# Minisumo_2018_Educatiu.net
KiCad netlist of a schematic drawn in EAGLE
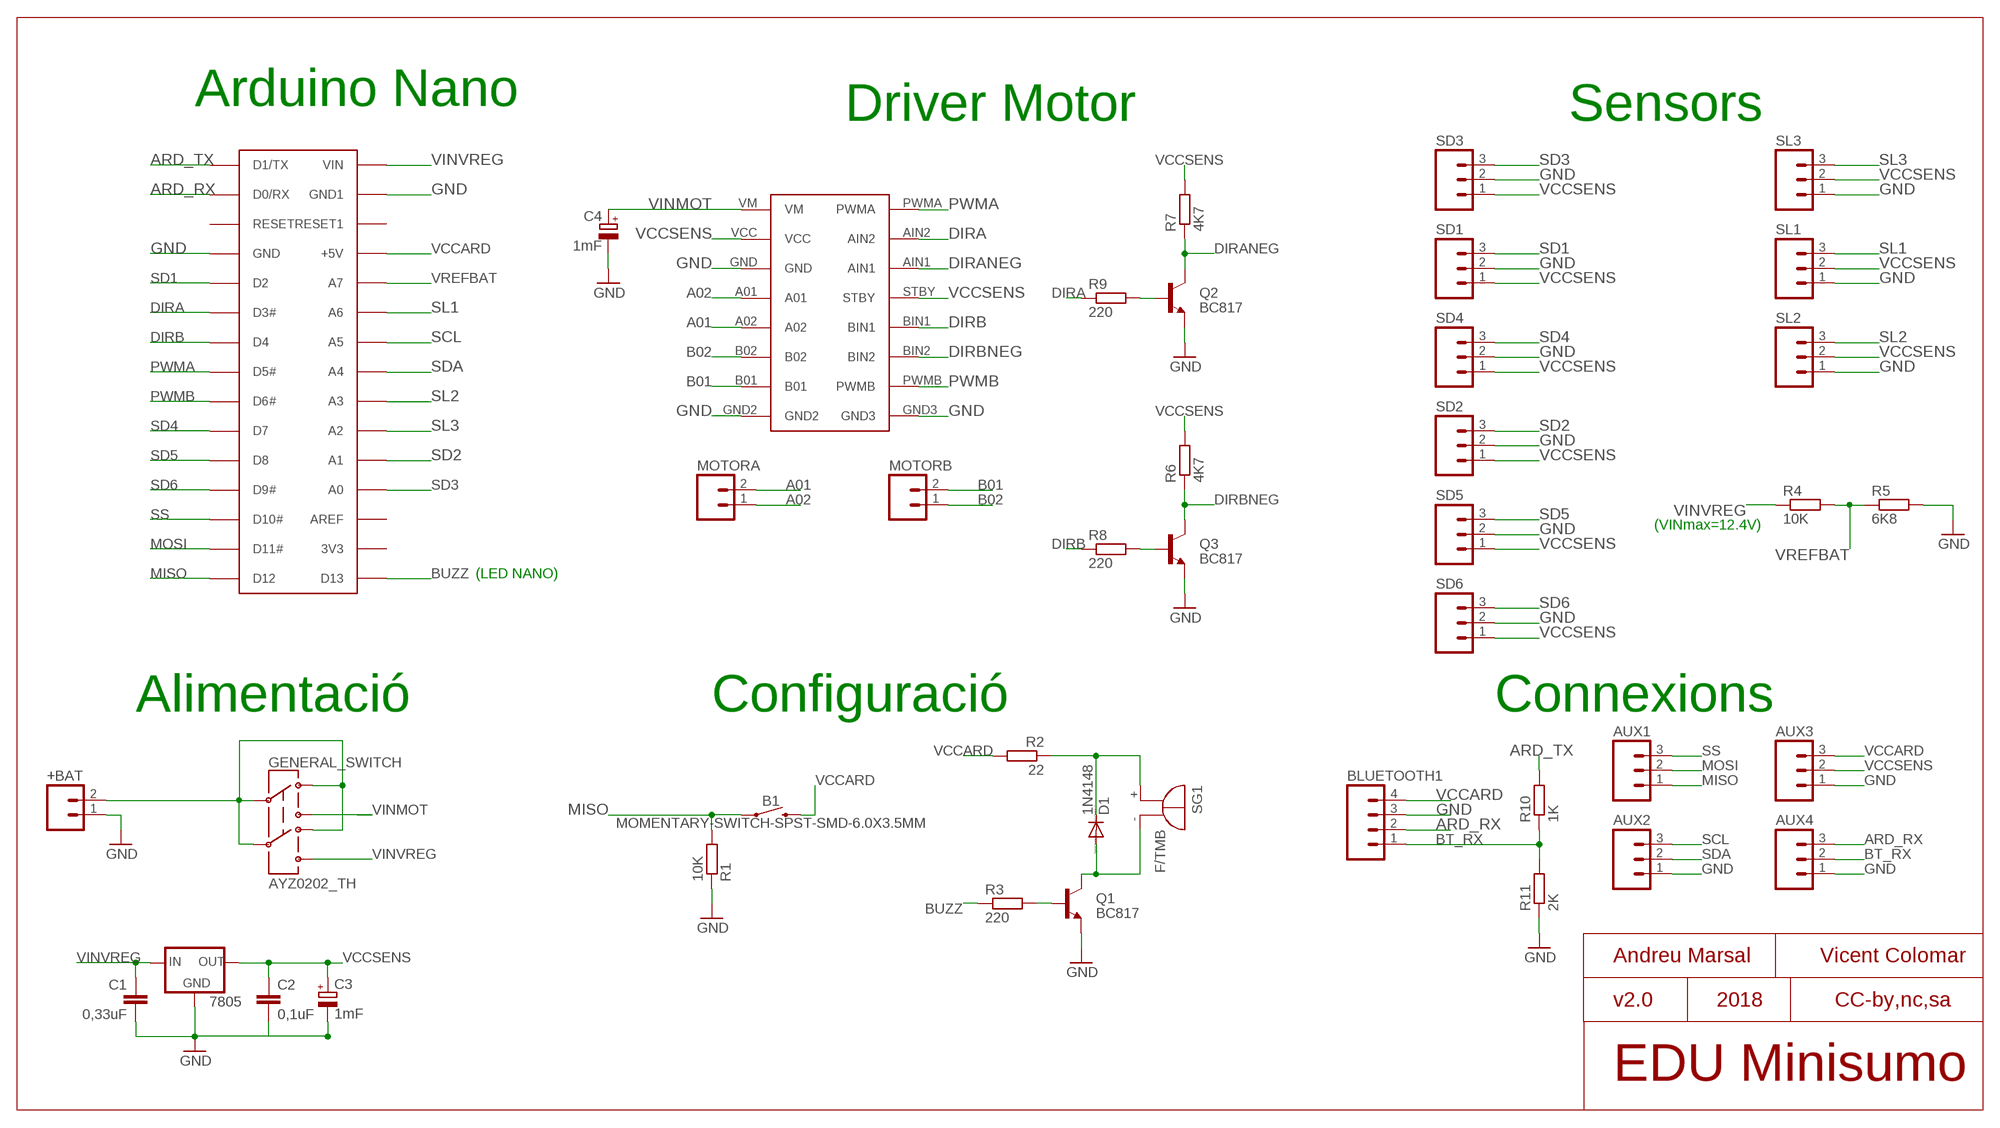
[diagram p0: schematic, sheet 1]
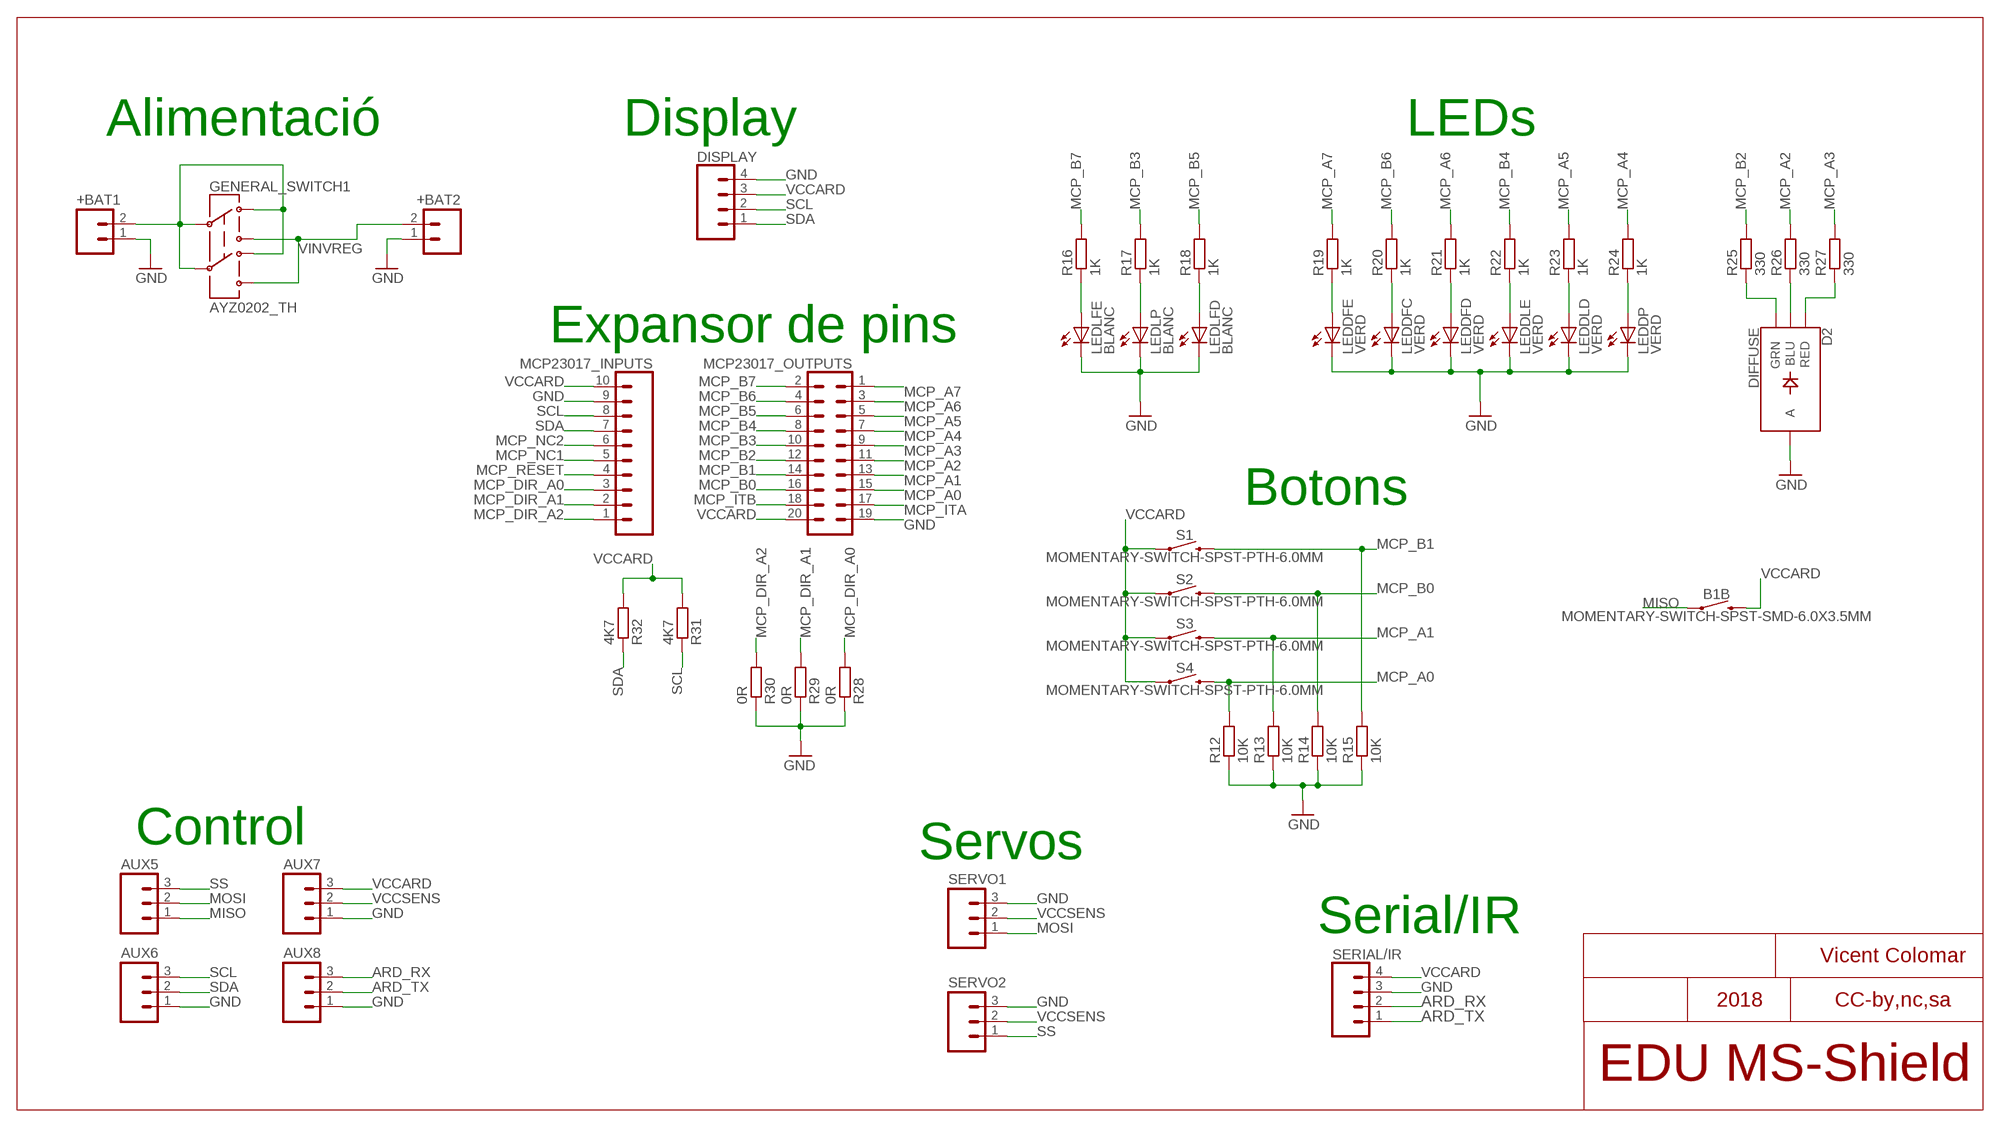
[diagram p1: schematic, sheet 2]

(export (version "E")
  (design (tool "Eeschema 10.0.6"))
  (components
    (comp (ref "+BAT")
      (value "M02LOCK_LONGPADS")
      (footprint "eagle-import:1X02_LOCK_LONGPADS")
      (libsource (lib "eagle-import") (part "M02LOCK_LONGPADS"))
    )
    (comp (ref "7805")
      (value "V_REG_78XXSINK")
      (footprint "eagle-import:TO220-IGO")
      (libsource (lib "eagle-import") (part "V_REG_78XXSINK"))
    )
    (comp (ref "AUX1")
      (value "M03PTH")
      (footprint "eagle-import:1X03")
      (libsource (lib "eagle-import") (part "M03PTH"))
    )
    (comp (ref "AUX2")
      (value "M03PTH")
      (footprint "eagle-import:1X03")
      (libsource (lib "eagle-import") (part "M03PTH"))
    )
    (comp (ref "AUX3")
      (value "M03PTH")
      (footprint "eagle-import:1X03")
      (libsource (lib "eagle-import") (part "M03PTH"))
    )
    (comp (ref "AUX4")
      (value "M03PTH")
      (footprint "eagle-import:1X03")
      (libsource (lib "eagle-import") (part "M03PTH"))
    )
    (comp (ref "B1")
      (value "MOMENTARY-SWITCH-SPST-SMD-6.0X3.5MM")
      (footprint "eagle-import:TACTILE_SWITCH_SMD_6.0X3.5MM")
      (libsource (lib "eagle-import") (part "MOMENTARY-SWITCH-SPST-SMD-6.0X3.5MM"))
    )
    (comp (ref "BLUETOOTH1")
      (value "M04PTH")
      (footprint "eagle-import:1X04")
      (libsource (lib "eagle-import") (part "M04PTH"))
    )
    (comp (ref "C1")
      (value "0,33uF")
      (footprint "eagle-import:C1206K")
      (libsource (lib "eagle-import") (part "C-EUC1206K"))
    )
    (comp (ref "C2")
      (value "0,1uF")
      (footprint "eagle-import:C1206K")
      (libsource (lib "eagle-import") (part "C-EUC1206K"))
    )
    (comp (ref "C3")
      (value "1mF")
      (footprint "eagle-import:E2,5-6")
      (libsource (lib "eagle-import") (part "CPOL-EUE2.5-6"))
    )
    (comp (ref "C4")
      (value "1mF")
      (footprint "eagle-import:E2,5-6")
      (libsource (lib "eagle-import") (part "CPOL-EUE2.5-6"))
    )
    (comp (ref "D1")
      (value "1N4148")
      (footprint "eagle-import:SOD106-R")
      (libsource (lib "eagle-import") (part "DIODE-SOD106-R"))
    )
    (comp (ref "GENERAL_SWITCH")
      (value "AYZ0202_TH")
      (footprint "eagle-import:AYZ0202_TH")
      (libsource (lib "eagle-import") (part "AYZ0202_TH"))
    )
    (comp (ref "MOTORA")
      (value "M023.5MM")
      (footprint "eagle-import:SCREWTERMINAL-3.5MM-2")
      (libsource (lib "eagle-import") (part "M023.5MM"))
    )
    (comp (ref "MOTORB")
      (value "M023.5MM")
      (footprint "eagle-import:SCREWTERMINAL-3.5MM-2")
      (libsource (lib "eagle-import") (part "M023.5MM"))
    )
    (comp (ref "Q1")
      (value "BC817")
      (footprint "eagle-import:TO-92")
      (libsource (lib "eagle-import") (part "TRANSISTOR_NPNTO92"))
    )
    (comp (ref "Q2")
      (value "BC817")
      (footprint "eagle-import:TO-92")
      (libsource (lib "eagle-import") (part "TRANSISTOR_NPNTO92"))
    )
    (comp (ref "Q3")
      (value "BC817")
      (footprint "eagle-import:TO-92")
      (libsource (lib "eagle-import") (part "TRANSISTOR_NPNTO92"))
    )
    (comp (ref "R1")
      (value "10K")
      (footprint "eagle-import:R1206")
      (libsource (lib "eagle-import") (part "resistor_348_R-EU_R1206"))
    )
    (comp (ref "R2")
      (value "22")
      (footprint "eagle-import:R1206")
      (libsource (lib "eagle-import") (part "resistor_348_R-EU_R1206"))
    )
    (comp (ref "R3")
      (value "220")
      (footprint "eagle-import:M1206")
      (libsource (lib "eagle-import") (part "R-EU_M1206"))
    )
    (comp (ref "R4")
      (value "10K")
      (footprint "eagle-import:R1206")
      (libsource (lib "eagle-import") (part "resistor_348_R-EU_R1206"))
    )
    (comp (ref "R5")
      (value "6K8")
      (footprint "eagle-import:R1206")
      (libsource (lib "eagle-import") (part "resistor_348_R-EU_R1206"))
    )
    (comp (ref "R6")
      (value "4K7")
      (footprint "eagle-import:M1206")
      (libsource (lib "eagle-import") (part "R-EU_M1206"))
    )
    (comp (ref "R7")
      (value "4K7")
      (footprint "eagle-import:M1206")
      (libsource (lib "eagle-import") (part "R-EU_M1206"))
    )
    (comp (ref "R8")
      (value "220")
      (footprint "eagle-import:M1206")
      (libsource (lib "eagle-import") (part "R-EU_M1206"))
    )
    (comp (ref "R9")
      (value "220")
      (footprint "eagle-import:M1206")
      (libsource (lib "eagle-import") (part "R-EU_M1206"))
    )
    (comp (ref "R10")
      (value "1K")
      (footprint "eagle-import:R1206")
      (libsource (lib "eagle-import") (part "resistor_348_R-EU_R1206"))
    )
    (comp (ref "R11")
      (value "2K")
      (footprint "eagle-import:R1206")
      (libsource (lib "eagle-import") (part "resistor_348_R-EU_R1206"))
    )
    (comp (ref "SD1")
      (value "M03PTH")
      (footprint "eagle-import:1X03")
      (libsource (lib "eagle-import") (part "M03PTH"))
    )
    (comp (ref "SD2")
      (value "M03PTH")
      (footprint "eagle-import:1X03")
      (libsource (lib "eagle-import") (part "M03PTH"))
    )
    (comp (ref "SD3")
      (value "M03PTH")
      (footprint "eagle-import:1X03")
      (libsource (lib "eagle-import") (part "M03PTH"))
    )
    (comp (ref "SD4")
      (value "M03PTH")
      (footprint "eagle-import:1X03")
      (libsource (lib "eagle-import") (part "M03PTH"))
    )
    (comp (ref "SD5")
      (value "M03PTH")
      (footprint "eagle-import:1X03")
      (libsource (lib "eagle-import") (part "M03PTH"))
    )
    (comp (ref "SD6")
      (value "M03PTH")
      (footprint "eagle-import:1X03")
      (libsource (lib "eagle-import") (part "M03PTH"))
    )
    (comp (ref "SG1")
      (value "F/TMB")
      (footprint "eagle-import:F_TMB")
      (libsource (lib "eagle-import") (part "F/TMB"))
    )
    (comp (ref "SL1")
      (value "M03PTH")
      (footprint "eagle-import:1X03")
      (libsource (lib "eagle-import") (part "M03PTH"))
    )
    (comp (ref "SL2")
      (value "M03PTH")
      (footprint "eagle-import:1X03")
      (libsource (lib "eagle-import") (part "M03PTH"))
    )
    (comp (ref "SL3")
      (value "M03PTH")
      (footprint "eagle-import:1X03")
      (libsource (lib "eagle-import") (part "M03PTH"))
    )
    (comp (ref "U$1")
      (value "ARDUINONANONOHOLES")
      (footprint "eagle-import:PDIP-32NOHOLES")
      (libsource (lib "eagle-import") (part "ARDUINONANONOHOLES"))
    )
    (comp (ref "U$2")
      (value "TB6612FNG_SPARKFUN")
      (footprint "eagle-import:TB6612FNG_SPARKFUN")
      (libsource (lib "eagle-import") (part "TB6612FNG_SPARKFUN"))
    )
    (comp (ref "+BAT1")
      (value "M02LOCK_LONGPADS")
      (footprint "eagle-import:1X02_LOCK_LONGPADS")
      (libsource (lib "eagle-import") (part "M02LOCK_LONGPADS"))
    )
    (comp (ref "+BAT2")
      (value "M02LOCK_LONGPADS")
      (footprint "eagle-import:1X02_LOCK_LONGPADS")
      (libsource (lib "eagle-import") (part "M02LOCK_LONGPADS"))
    )
    (comp (ref "AUX5")
      (value "M03PTH")
      (footprint "eagle-import:1X03")
      (libsource (lib "eagle-import") (part "M03PTH"))
    )
    (comp (ref "AUX6")
      (value "M03PTH")
      (footprint "eagle-import:1X03")
      (libsource (lib "eagle-import") (part "M03PTH"))
    )
    (comp (ref "AUX7")
      (value "M03PTH")
      (footprint "eagle-import:1X03")
      (libsource (lib "eagle-import") (part "M03PTH"))
    )
    (comp (ref "AUX8")
      (value "M03PTH")
      (footprint "eagle-import:1X03")
      (libsource (lib "eagle-import") (part "M03PTH"))
    )
    (comp (ref "B1B")
      (value "MOMENTARY-SWITCH-SPST-SMD-6.0X3.5MM")
      (footprint "eagle-import:TACTILE_SWITCH_SMD_6.0X3.5MM")
      (libsource (lib "eagle-import") (part "MOMENTARY-SWITCH-SPST-SMD-6.0X3.5MM"))
    )
    (comp (ref "D2")
      (value "DIFFUSE")
      (footprint "eagle-import:LED-RGB-THRU")
      (libsource (lib "eagle-import") (part "LED-RGB-CADIFFUSE"))
    )
    (comp (ref "DISPLAY")
      (value "CONN_04")
      (footprint "eagle-import:1X04")
      (libsource (lib "eagle-import") (part "CONN_04"))
    )
    (comp (ref "GENERAL_SWITCH1")
      (value "AYZ0202_TH")
      (footprint "eagle-import:AYZ0202_TH")
      (libsource (lib "eagle-import") (part "AYZ0202_TH"))
    )
    (comp (ref "LEDDFC")
      (value "VERD")
      (footprint "eagle-import:1206")
      (libsource (lib "eagle-import") (part "LEDSMT1206"))
    )
    (comp (ref "LEDDFD")
      (value "VERD")
      (footprint "eagle-import:1206")
      (libsource (lib "eagle-import") (part "LEDSMT1206"))
    )
    (comp (ref "LEDDFE")
      (value "VERD")
      (footprint "eagle-import:1206")
      (libsource (lib "eagle-import") (part "LEDSMT1206"))
    )
    (comp (ref "LEDDLD")
      (value "VERD")
      (footprint "eagle-import:1206")
      (libsource (lib "eagle-import") (part "LEDSMT1206"))
    )
    (comp (ref "LEDDLE")
      (value "VERD")
      (footprint "eagle-import:1206")
      (libsource (lib "eagle-import") (part "LEDSMT1206"))
    )
    (comp (ref "LEDDP")
      (value "VERD")
      (footprint "eagle-import:1206")
      (libsource (lib "eagle-import") (part "LEDSMT1206"))
    )
    (comp (ref "LEDLFD")
      (value "BLANC")
      (footprint "eagle-import:1206")
      (libsource (lib "eagle-import") (part "LEDSMT1206"))
    )
    (comp (ref "LEDLFE")
      (value "BLANC")
      (footprint "eagle-import:1206")
      (libsource (lib "eagle-import") (part "LEDSMT1206"))
    )
    (comp (ref "LEDLP")
      (value "BLANC")
      (footprint "eagle-import:1206")
      (libsource (lib "eagle-import") (part "LEDSMT1206"))
    )
    (comp (ref "MCP23017_INPUTS")
      (value "CONN_10\"")
      (footprint "eagle-import:1X10")
      (libsource (lib "eagle-import") (part "CONN_10{dblquote}"))
    )
    (comp (ref "MCP23017_OUTPUTS")
      (value "CONN_10X2")
      (footprint "eagle-import:2X10")
      (libsource (lib "eagle-import") (part "CONN_10X2"))
    )
    (comp (ref "R12")
      (value "10K")
      (footprint "eagle-import:M1206")
      (libsource (lib "eagle-import") (part "R-EU_M1206"))
    )
    (comp (ref "R13")
      (value "10K")
      (footprint "eagle-import:M1206")
      (libsource (lib "eagle-import") (part "R-EU_M1206"))
    )
    (comp (ref "R14")
      (value "10K")
      (footprint "eagle-import:M1206")
      (libsource (lib "eagle-import") (part "R-EU_M1206"))
    )
    (comp (ref "R15")
      (value "10K")
      (footprint "eagle-import:M1206")
      (libsource (lib "eagle-import") (part "R-EU_M1206"))
    )
    (comp (ref "R16")
      (value "1K")
      (footprint "eagle-import:M1206")
      (libsource (lib "eagle-import") (part "R-EU_M1206"))
    )
    (comp (ref "R17")
      (value "1K")
      (footprint "eagle-import:M1206")
      (libsource (lib "eagle-import") (part "R-EU_M1206"))
    )
    (comp (ref "R18")
      (value "1K")
      (footprint "eagle-import:M1206")
      (libsource (lib "eagle-import") (part "R-EU_M1206"))
    )
    (comp (ref "R19")
      (value "1K")
      (footprint "eagle-import:M1206")
      (libsource (lib "eagle-import") (part "R-EU_M1206"))
    )
    (comp (ref "R20")
      (value "1K")
      (footprint "eagle-import:M1206")
      (libsource (lib "eagle-import") (part "R-EU_M1206"))
    )
    (comp (ref "R21")
      (value "1K")
      (footprint "eagle-import:M1206")
      (libsource (lib "eagle-import") (part "R-EU_M1206"))
    )
    (comp (ref "R22")
      (value "1K")
      (footprint "eagle-import:M1206")
      (libsource (lib "eagle-import") (part "R-EU_M1206"))
    )
    (comp (ref "R23")
      (value "1K")
      (footprint "eagle-import:M1206")
      (libsource (lib "eagle-import") (part "R-EU_M1206"))
    )
    (comp (ref "R24")
      (value "1K")
      (footprint "eagle-import:M1206")
      (libsource (lib "eagle-import") (part "R-EU_M1206"))
    )
    (comp (ref "R25")
      (value "330")
      (footprint "eagle-import:M1206")
      (libsource (lib "eagle-import") (part "R-EU_M1206"))
    )
    (comp (ref "R26")
      (value "330")
      (footprint "eagle-import:M1206")
      (libsource (lib "eagle-import") (part "R-EU_M1206"))
    )
    (comp (ref "R27")
      (value "330")
      (footprint "eagle-import:M1206")
      (libsource (lib "eagle-import") (part "R-EU_M1206"))
    )
    (comp (ref "R28")
      (value "0R")
      (footprint "eagle-import:M1206")
      (libsource (lib "eagle-import") (part "R-EU_M1206"))
    )
    (comp (ref "R29")
      (value "0R")
      (footprint "eagle-import:M1206")
      (libsource (lib "eagle-import") (part "R-EU_M1206"))
    )
    (comp (ref "R30")
      (value "0R")
      (footprint "eagle-import:M1206")
      (libsource (lib "eagle-import") (part "R-EU_M1206"))
    )
    (comp (ref "R31")
      (value "4K7")
      (footprint "eagle-import:M1206")
      (libsource (lib "eagle-import") (part "R-EU_M1206"))
    )
    (comp (ref "R32")
      (value "4K7")
      (footprint "eagle-import:M1206")
      (libsource (lib "eagle-import") (part "R-EU_M1206"))
    )
    (comp (ref "S1")
      (value "MOMENTARY-SWITCH-SPST-PTH-6.0MM")
      (footprint "eagle-import:TACTILE_SWITCH_PTH_6.0MM")
      (libsource (lib "eagle-import") (part "MOMENTARY-SWITCH-SPST-PTH-6.0MM"))
    )
    (comp (ref "S2")
      (value "MOMENTARY-SWITCH-SPST-PTH-6.0MM")
      (footprint "eagle-import:TACTILE_SWITCH_PTH_6.0MM")
      (libsource (lib "eagle-import") (part "MOMENTARY-SWITCH-SPST-PTH-6.0MM"))
    )
    (comp (ref "S3")
      (value "MOMENTARY-SWITCH-SPST-PTH-6.0MM")
      (footprint "eagle-import:TACTILE_SWITCH_PTH_6.0MM")
      (libsource (lib "eagle-import") (part "MOMENTARY-SWITCH-SPST-PTH-6.0MM"))
    )
    (comp (ref "S4")
      (value "MOMENTARY-SWITCH-SPST-PTH-6.0MM")
      (footprint "eagle-import:TACTILE_SWITCH_PTH_6.0MM")
      (libsource (lib "eagle-import") (part "MOMENTARY-SWITCH-SPST-PTH-6.0MM"))
    )
    (comp (ref "SERIAL/IR")
      (value "CONN_04")
      (footprint "eagle-import:1X04")
      (libsource (lib "eagle-import") (part "CONN_04"))
    )
    (comp (ref "SERVO1")
      (value "M03PTH")
      (footprint "eagle-import:1X03")
      (libsource (lib "eagle-import") (part "M03PTH"))
    )
    (comp (ref "SERVO2")
      (value "M03PTH")
      (footprint "eagle-import:1X03")
      (libsource (lib "eagle-import") (part "M03PTH"))
    )
  )
  (nets
    (net (code "1") (name "A01") (class "Default")
      (node (ref "MOTORA") (pin "2") (pinfunction "2_2") (pintype "passive"))
      (node (ref "U$2") (pin "A02") (pinfunction "A02_A02") (pintype "bidirectional"))
    )
    (net (code "2") (name "A02") (class "Default")
      (node (ref "MOTORA") (pin "1") (pinfunction "1_1") (pintype "passive"))
      (node (ref "U$2") (pin "A01") (pinfunction "A01_A01") (pintype "bidirectional"))
    )
    (net (code "3") (name "ARD_RX") (class "Default")
      (node (ref "AUX4") (pin "3") (pinfunction "3_3") (pintype "passive"))
      (node (ref "AUX8") (pin "3") (pinfunction "3_3") (pintype "passive"))
      (node (ref "BLUETOOTH1") (pin "2") (pinfunction "2_2") (pintype "passive"))
      (node (ref "SERIAL/IR") (pin "2") (pinfunction "2_2") (pintype "passive"))
      (node (ref "U$1") (pin "D0/RX") (pinfunction "D0/RX_D0/RX") (pintype "bidirectional"))
    )
    (net (code "4") (name "ARD_TX") (class "Default")
      (node (ref "AUX8") (pin "2") (pinfunction "2_2") (pintype "passive"))
      (node (ref "R10") (pin "2") (pinfunction "2_2") (pintype "passive"))
      (node (ref "SERIAL/IR") (pin "1") (pinfunction "1_1") (pintype "passive"))
      (node (ref "U$1") (pin "D1/TX") (pinfunction "D1/TX_D1/TX") (pintype "bidirectional"))
    )
    (net (code "5") (name "B01") (class "Default")
      (node (ref "MOTORB") (pin "2") (pinfunction "2_2") (pintype "passive"))
      (node (ref "U$2") (pin "B01") (pinfunction "B01_B01") (pintype "bidirectional"))
    )
    (net (code "6") (name "B02") (class "Default")
      (node (ref "MOTORB") (pin "1") (pinfunction "1_1") (pintype "passive"))
      (node (ref "U$2") (pin "B02") (pinfunction "B02_B02") (pintype "bidirectional"))
    )
    (net (code "7") (name "BT_RX") (class "Default")
      (node (ref "AUX4") (pin "2") (pinfunction "2_2") (pintype "passive"))
      (node (ref "BLUETOOTH1") (pin "1") (pinfunction "1_1") (pintype "passive"))
      (node (ref "R10") (pin "1") (pinfunction "1_1") (pintype "passive"))
      (node (ref "R11") (pin "2") (pinfunction "2_2") (pintype "passive"))
    )
    (net (code "8") (name "BUZZ") (class "Default")
      (node (ref "R3") (pin "1") (pinfunction "1_1") (pintype "passive"))
      (node (ref "U$1") (pin "D13") (pinfunction "D13_D13") (pintype "bidirectional"))
    )
    (net (code "9") (name "DIRA") (class "Default")
      (node (ref "R9") (pin "1") (pinfunction "1_1") (pintype "passive"))
      (node (ref "U$1") (pin "D3") (pinfunction "D3#_D3") (pintype "bidirectional"))
      (node (ref "U$2") (pin "AIN2") (pinfunction "AIN2_AIN2") (pintype "bidirectional"))
    )
    (net (code "10") (name "DIRANEG") (class "Default")
      (node (ref "Q2") (pin "3") (pinfunction "C_3") (pintype "passive"))
      (node (ref "R7") (pin "1") (pinfunction "1_1") (pintype "passive"))
      (node (ref "U$2") (pin "AIN1") (pinfunction "AIN1_AIN1") (pintype "bidirectional"))
    )
    (net (code "11") (name "DIRB") (class "Default")
      (node (ref "R8") (pin "1") (pinfunction "1_1") (pintype "passive"))
      (node (ref "U$1") (pin "D4") (pinfunction "D4_D4") (pintype "bidirectional"))
      (node (ref "U$2") (pin "BIN1") (pinfunction "BIN1_BIN1") (pintype "bidirectional"))
    )
    (net (code "12") (name "DIRBNEG") (class "Default")
      (node (ref "Q3") (pin "3") (pinfunction "C_3") (pintype "passive"))
      (node (ref "R6") (pin "1") (pinfunction "1_1") (pintype "passive"))
      (node (ref "U$2") (pin "BIN2") (pinfunction "BIN2_BIN2") (pintype "bidirectional"))
    )
    (net (code "13") (name "GND") (class "Default")
      (node (ref "+BAT") (pin "1") (pinfunction "1_1") (pintype "passive"))
      (node (ref "+BAT1") (pin "1") (pinfunction "1_1") (pintype "passive"))
      (node (ref "+BAT2") (pin "1") (pinfunction "1_1") (pintype "passive"))
      (node (ref "7805") (pin "GND") (pinfunction "GND_GND") (pintype "input"))
      (node (ref "AUX2") (pin "1") (pinfunction "1_1") (pintype "passive"))
      (node (ref "AUX3") (pin "1") (pinfunction "1_1") (pintype "passive"))
      (node (ref "AUX4") (pin "1") (pinfunction "1_1") (pintype "passive"))
      (node (ref "AUX6") (pin "1") (pinfunction "1_1") (pintype "passive"))
      (node (ref "AUX7") (pin "1") (pinfunction "1_1") (pintype "passive"))
      (node (ref "AUX8") (pin "1") (pinfunction "1_1") (pintype "passive"))
      (node (ref "BLUETOOTH1") (pin "3") (pinfunction "3_3") (pintype "passive"))
      (node (ref "C1") (pin "2") (pinfunction "2_2") (pintype "passive"))
      (node (ref "C2") (pin "2") (pinfunction "2_2") (pintype "passive"))
      (node (ref "C3") (pin "-") (pinfunction "-_-") (pintype "passive"))
      (node (ref "C4") (pin "-") (pinfunction "-_-") (pintype "passive"))
      (node (ref "D2") (pin "2") (pinfunction "A_2") (pintype "bidirectional"))
      (node (ref "DISPLAY") (pin "4") (pinfunction "4_4") (pintype "passive"))
      (node (ref "LEDDFC") (pin "C") (pinfunction "C_C") (pintype "passive"))
      (node (ref "LEDDFD") (pin "C") (pinfunction "C_C") (pintype "passive"))
      (node (ref "LEDDFE") (pin "C") (pinfunction "C_C") (pintype "passive"))
      (node (ref "LEDDLD") (pin "C") (pinfunction "C_C") (pintype "passive"))
      (node (ref "LEDDLE") (pin "C") (pinfunction "C_C") (pintype "passive"))
      (node (ref "LEDDP") (pin "C") (pinfunction "C_C") (pintype "passive"))
      (node (ref "LEDLFD") (pin "C") (pinfunction "C_C") (pintype "passive"))
      (node (ref "LEDLFE") (pin "C") (pinfunction "C_C") (pintype "passive"))
      (node (ref "LEDLP") (pin "C") (pinfunction "C_C") (pintype "passive"))
      (node (ref "MCP23017_INPUTS") (pin "9") (pinfunction "9_9") (pintype "passive"))
      (node (ref "MCP23017_OUTPUTS") (pin "19") (pinfunction "19_19") (pintype "passive"))
      (node (ref "Q1") (pin "1") (pinfunction "E_1") (pintype "passive"))
      (node (ref "Q2") (pin "1") (pinfunction "E_1") (pintype "passive"))
      (node (ref "Q3") (pin "1") (pinfunction "E_1") (pintype "passive"))
      (node (ref "R1") (pin "1") (pinfunction "1_1") (pintype "passive"))
      (node (ref "R11") (pin "1") (pinfunction "1_1") (pintype "passive"))
      (node (ref "R12") (pin "1") (pinfunction "1_1") (pintype "passive"))
      (node (ref "R13") (pin "1") (pinfunction "1_1") (pintype "passive"))
      (node (ref "R14") (pin "1") (pinfunction "1_1") (pintype "passive"))
      (node (ref "R15") (pin "1") (pinfunction "1_1") (pintype "passive"))
      (node (ref "R28") (pin "1") (pinfunction "1_1") (pintype "passive"))
      (node (ref "R29") (pin "1") (pinfunction "1_1") (pintype "passive"))
      (node (ref "R30") (pin "1") (pinfunction "1_1") (pintype "passive"))
      (node (ref "R5") (pin "2") (pinfunction "2_2") (pintype "passive"))
      (node (ref "SD1") (pin "2") (pinfunction "2_2") (pintype "passive"))
      (node (ref "SD2") (pin "2") (pinfunction "2_2") (pintype "passive"))
      (node (ref "SD3") (pin "2") (pinfunction "2_2") (pintype "passive"))
      (node (ref "SD4") (pin "2") (pinfunction "2_2") (pintype "passive"))
      (node (ref "SD5") (pin "2") (pinfunction "2_2") (pintype "passive"))
      (node (ref "SD6") (pin "2") (pinfunction "2_2") (pintype "passive"))
      (node (ref "SERIAL/IR") (pin "3") (pinfunction "3_3") (pintype "passive"))
      (node (ref "SERVO1") (pin "3") (pinfunction "3_3") (pintype "passive"))
      (node (ref "SERVO2") (pin "3") (pinfunction "3_3") (pintype "passive"))
      (node (ref "SL1") (pin "1") (pinfunction "1_1") (pintype "passive"))
      (node (ref "SL2") (pin "1") (pinfunction "1_1") (pintype "passive"))
      (node (ref "SL3") (pin "1") (pinfunction "1_1") (pintype "passive"))
      (node (ref "U$1") (pin "GND") (pinfunction "GND_GND") (pintype "bidirectional"))
      (node (ref "U$1") (pin "GND1") (pinfunction "GND1_GND1") (pintype "bidirectional"))
      (node (ref "U$2") (pin "GND") (pinfunction "GND_GND") (pintype "bidirectional"))
      (node (ref "U$2") (pin "GND2") (pinfunction "GND2_GND2") (pintype "bidirectional"))
      (node (ref "U$2") (pin "GND3") (pinfunction "GND3_GND3") (pintype "bidirectional"))
    )
    (net (code "14") (name "MCP_A0") (class "Default")
      (node (ref "MCP23017_OUTPUTS") (pin "15") (pinfunction "15_15") (pintype "passive"))
      (node (ref "R12") (pin "2") (pinfunction "2_2") (pintype "passive"))
      (node (ref "S4") (pin "3") (pinfunction "2_3") (pintype "passive"))
    )
    (net (code "15") (name "MCP_A1") (class "Default")
      (node (ref "MCP23017_OUTPUTS") (pin "13") (pinfunction "13_13") (pintype "passive"))
      (node (ref "R13") (pin "2") (pinfunction "2_2") (pintype "passive"))
      (node (ref "S3") (pin "3") (pinfunction "2_3") (pintype "passive"))
    )
    (net (code "16") (name "MCP_A2") (class "Default")
      (node (ref "MCP23017_OUTPUTS") (pin "11") (pinfunction "11_11") (pintype "passive"))
      (node (ref "R26") (pin "2") (pinfunction "2_2") (pintype "passive"))
    )
    (net (code "17") (name "MCP_A3") (class "Default")
      (node (ref "MCP23017_OUTPUTS") (pin "9") (pinfunction "9_9") (pintype "passive"))
      (node (ref "R27") (pin "2") (pinfunction "2_2") (pintype "passive"))
    )
    (net (code "18") (name "MCP_A4") (class "Default")
      (node (ref "MCP23017_OUTPUTS") (pin "7") (pinfunction "7_7") (pintype "passive"))
      (node (ref "R24") (pin "2") (pinfunction "2_2") (pintype "passive"))
    )
    (net (code "19") (name "MCP_A5") (class "Default")
      (node (ref "MCP23017_OUTPUTS") (pin "5") (pinfunction "5_5") (pintype "passive"))
      (node (ref "R23") (pin "2") (pinfunction "2_2") (pintype "passive"))
    )
    (net (code "20") (name "MCP_A6") (class "Default")
      (node (ref "MCP23017_OUTPUTS") (pin "3") (pinfunction "3_3") (pintype "passive"))
      (node (ref "R21") (pin "2") (pinfunction "2_2") (pintype "passive"))
    )
    (net (code "21") (name "MCP_A7") (class "Default")
      (node (ref "MCP23017_OUTPUTS") (pin "1") (pinfunction "1_1") (pintype "passive"))
      (node (ref "R19") (pin "2") (pinfunction "2_2") (pintype "passive"))
    )
    (net (code "22") (name "MCP_B0") (class "Default")
      (node (ref "MCP23017_OUTPUTS") (pin "16") (pinfunction "16_16") (pintype "passive"))
      (node (ref "R14") (pin "2") (pinfunction "2_2") (pintype "passive"))
      (node (ref "S2") (pin "3") (pinfunction "2_3") (pintype "passive"))
    )
    (net (code "23") (name "MCP_B1") (class "Default")
      (node (ref "MCP23017_OUTPUTS") (pin "14") (pinfunction "14_14") (pintype "passive"))
      (node (ref "R15") (pin "2") (pinfunction "2_2") (pintype "passive"))
      (node (ref "S1") (pin "3") (pinfunction "2_3") (pintype "passive"))
    )
    (net (code "24") (name "MCP_B2") (class "Default")
      (node (ref "MCP23017_OUTPUTS") (pin "12") (pinfunction "12_12") (pintype "passive"))
      (node (ref "R25") (pin "2") (pinfunction "2_2") (pintype "passive"))
    )
    (net (code "25") (name "MCP_B3") (class "Default")
      (node (ref "MCP23017_OUTPUTS") (pin "10") (pinfunction "10_10") (pintype "passive"))
      (node (ref "R17") (pin "2") (pinfunction "2_2") (pintype "passive"))
    )
    (net (code "26") (name "MCP_B4") (class "Default")
      (node (ref "MCP23017_OUTPUTS") (pin "8") (pinfunction "8_8") (pintype "passive"))
      (node (ref "R22") (pin "2") (pinfunction "2_2") (pintype "passive"))
    )
    (net (code "27") (name "MCP_B5") (class "Default")
      (node (ref "MCP23017_OUTPUTS") (pin "6") (pinfunction "6_6") (pintype "passive"))
      (node (ref "R18") (pin "2") (pinfunction "2_2") (pintype "passive"))
    )
    (net (code "28") (name "MCP_B6") (class "Default")
      (node (ref "MCP23017_OUTPUTS") (pin "4") (pinfunction "4_4") (pintype "passive"))
      (node (ref "R20") (pin "2") (pinfunction "2_2") (pintype "passive"))
    )
    (net (code "29") (name "MCP_B7") (class "Default")
      (node (ref "MCP23017_OUTPUTS") (pin "2") (pinfunction "2_2") (pintype "passive"))
      (node (ref "R16") (pin "2") (pinfunction "2_2") (pintype "passive"))
    )
    (net (code "30") (name "MCP_DIR_A0") (class "Default")
      (node (ref "MCP23017_INPUTS") (pin "3") (pinfunction "3_3") (pintype "passive"))
      (node (ref "R28") (pin "2") (pinfunction "2_2") (pintype "passive"))
    )
    (net (code "31") (name "MCP_DIR_A1") (class "Default")
      (node (ref "MCP23017_INPUTS") (pin "2") (pinfunction "2_2") (pintype "passive"))
      (node (ref "R29") (pin "2") (pinfunction "2_2") (pintype "passive"))
    )
    (net (code "32") (name "MCP_DIR_A2") (class "Default")
      (node (ref "MCP23017_INPUTS") (pin "1") (pinfunction "1_1") (pintype "passive"))
      (node (ref "R30") (pin "2") (pinfunction "2_2") (pintype "passive"))
    )
    (net (code "33") (name "MCP_ITA") (class "Default")
      (node (ref "MCP23017_OUTPUTS") (pin "17") (pinfunction "17_17") (pintype "passive"))
    )
    (net (code "34") (name "MCP_ITB") (class "Default")
      (node (ref "MCP23017_OUTPUTS") (pin "18") (pinfunction "18_18") (pintype "passive"))
    )
    (net (code "35") (name "MCP_NC1") (class "Default")
      (node (ref "MCP23017_INPUTS") (pin "5") (pinfunction "5_5") (pintype "passive"))
    )
    (net (code "36") (name "MCP_NC2") (class "Default")
      (node (ref "MCP23017_INPUTS") (pin "6") (pinfunction "6_6") (pintype "passive"))
    )
    (net (code "37") (name "MCP_RESET") (class "Default")
      (node (ref "MCP23017_INPUTS") (pin "4") (pinfunction "4_4") (pintype "passive"))
    )
    (net (code "38") (name "MISO") (class "Default")
      (node (ref "AUX1") (pin "1") (pinfunction "1_1") (pintype "passive"))
      (node (ref "AUX5") (pin "1") (pinfunction "1_1") (pintype "passive"))
      (node (ref "B1") (pin "1") (pinfunction "1_1") (pintype "passive"))
      (node (ref "B1B") (pin "1") (pinfunction "1_1") (pintype "passive"))
      (node (ref "R1") (pin "2") (pinfunction "2_2") (pintype "passive"))
      (node (ref "U$1") (pin "D12") (pinfunction "D12_D12") (pintype "bidirectional"))
    )
    (net (code "39") (name "MOSI") (class "Default")
      (node (ref "AUX1") (pin "2") (pinfunction "2_2") (pintype "passive"))
      (node (ref "AUX5") (pin "2") (pinfunction "2_2") (pintype "passive"))
      (node (ref "SERVO1") (pin "1") (pinfunction "1_1") (pintype "passive"))
      (node (ref "U$1") (pin "D11") (pinfunction "D11#_D11") (pintype "bidirectional"))
    )
    (net (code "40") (name "Net-(+BAT-Pad2)") (class "Default")
      (node (ref "+BAT") (pin "2") (pinfunction "2_2") (pintype "passive"))
      (node (ref "GENERAL_SWITCH") (pin "C1") (pinfunction "C1_C1") (pintype "bidirectional"))
      (node (ref "GENERAL_SWITCH") (pin "C2") (pinfunction "C2_C2") (pintype "bidirectional"))
      (node (ref "GENERAL_SWITCH") (pin "D1") (pinfunction "D1_D1") (pintype "bidirectional"))
      (node (ref "GENERAL_SWITCH") (pin "D2") (pinfunction "D2_D2") (pintype "bidirectional"))
    )
    (net (code "41") (name "Net-(+BAT1-Pad2)") (class "Default")
      (node (ref "+BAT1") (pin "2") (pinfunction "2_2") (pintype "passive"))
      (node (ref "GENERAL_SWITCH1") (pin "C1") (pinfunction "C1_C1") (pintype "bidirectional"))
      (node (ref "GENERAL_SWITCH1") (pin "C2") (pinfunction "C2_C2") (pintype "bidirectional"))
      (node (ref "GENERAL_SWITCH1") (pin "D1") (pinfunction "D1_D1") (pintype "bidirectional"))
      (node (ref "GENERAL_SWITCH1") (pin "D2") (pinfunction "D2_D2") (pintype "bidirectional"))
    )
    (net (code "42") (name "Net-(D1-PadC)") (class "Default")
      (node (ref "D1") (pin "C") (pinfunction "C_C") (pintype "passive"))
      (node (ref "R2") (pin "1") (pinfunction "1_1") (pintype "passive"))
      (node (ref "SG1") (pin "+") (pinfunction "+_+") (pintype "passive"))
    )
    (net (code "43") (name "Net-(D2-BLU)") (class "Default")
      (node (ref "D2") (pin "4") (pinfunction "BLU_4") (pintype "bidirectional"))
      (node (ref "R26") (pin "1") (pinfunction "1_1") (pintype "passive"))
    )
    (net (code "44") (name "Net-(D2-GRN)") (class "Default")
      (node (ref "D2") (pin "3") (pinfunction "GRN_3") (pintype "bidirectional"))
      (node (ref "R25") (pin "1") (pinfunction "1_1") (pintype "passive"))
    )
    (net (code "45") (name "Net-(D2-RED)") (class "Default")
      (node (ref "D2") (pin "1") (pinfunction "RED_1") (pintype "bidirectional"))
      (node (ref "R27") (pin "1") (pinfunction "1_1") (pintype "passive"))
    )
    (net (code "46") (name "Net-(LEDDFC-PadA)") (class "Default")
      (node (ref "LEDDFC") (pin "A") (pinfunction "A_A") (pintype "passive"))
      (node (ref "R20") (pin "1") (pinfunction "1_1") (pintype "passive"))
    )
    (net (code "47") (name "Net-(LEDDFD-PadA)") (class "Default")
      (node (ref "LEDDFD") (pin "A") (pinfunction "A_A") (pintype "passive"))
      (node (ref "R21") (pin "1") (pinfunction "1_1") (pintype "passive"))
    )
    (net (code "48") (name "Net-(LEDDFE-PadA)") (class "Default")
      (node (ref "LEDDFE") (pin "A") (pinfunction "A_A") (pintype "passive"))
      (node (ref "R19") (pin "1") (pinfunction "1_1") (pintype "passive"))
    )
    (net (code "49") (name "Net-(LEDDLD-PadA)") (class "Default")
      (node (ref "LEDDLD") (pin "A") (pinfunction "A_A") (pintype "passive"))
      (node (ref "R23") (pin "1") (pinfunction "1_1") (pintype "passive"))
    )
    (net (code "50") (name "Net-(LEDDLE-PadA)") (class "Default")
      (node (ref "LEDDLE") (pin "A") (pinfunction "A_A") (pintype "passive"))
      (node (ref "R22") (pin "1") (pinfunction "1_1") (pintype "passive"))
    )
    (net (code "51") (name "Net-(LEDDP-PadA)") (class "Default")
      (node (ref "LEDDP") (pin "A") (pinfunction "A_A") (pintype "passive"))
      (node (ref "R24") (pin "1") (pinfunction "1_1") (pintype "passive"))
    )
    (net (code "52") (name "Net-(LEDLFD-PadA)") (class "Default")
      (node (ref "LEDLFD") (pin "A") (pinfunction "A_A") (pintype "passive"))
      (node (ref "R18") (pin "1") (pinfunction "1_1") (pintype "passive"))
    )
    (net (code "53") (name "Net-(LEDLFE-PadA)") (class "Default")
      (node (ref "LEDLFE") (pin "A") (pinfunction "A_A") (pintype "passive"))
      (node (ref "R16") (pin "1") (pinfunction "1_1") (pintype "passive"))
    )
    (net (code "54") (name "Net-(LEDLP-PadA)") (class "Default")
      (node (ref "LEDLP") (pin "A") (pinfunction "A_A") (pintype "passive"))
      (node (ref "R17") (pin "1") (pinfunction "1_1") (pintype "passive"))
    )
    (net (code "55") (name "Net-(Q1-B)") (class "Default")
      (node (ref "Q1") (pin "2") (pinfunction "B_2") (pintype "passive"))
      (node (ref "R3") (pin "2") (pinfunction "2_2") (pintype "passive"))
    )
    (net (code "56") (name "Net-(Q1-C)") (class "Default")
      (node (ref "D1") (pin "A") (pinfunction "A_A") (pintype "passive"))
      (node (ref "Q1") (pin "3") (pinfunction "C_3") (pintype "passive"))
      (node (ref "SG1") (pin "-") (pinfunction "-_-") (pintype "passive"))
    )
    (net (code "57") (name "Net-(Q2-B)") (class "Default")
      (node (ref "Q2") (pin "2") (pinfunction "B_2") (pintype "passive"))
      (node (ref "R9") (pin "2") (pinfunction "2_2") (pintype "passive"))
    )
    (net (code "58") (name "Net-(Q3-B)") (class "Default")
      (node (ref "Q3") (pin "2") (pinfunction "B_2") (pintype "passive"))
      (node (ref "R8") (pin "2") (pinfunction "2_2") (pintype "passive"))
    )
    (net (code "59") (name "PWMA") (class "Default")
      (node (ref "U$1") (pin "D5") (pinfunction "D5#_D5") (pintype "bidirectional"))
      (node (ref "U$2") (pin "PWMA") (pinfunction "PWMA_PWMA") (pintype "bidirectional"))
    )
    (net (code "60") (name "PWMB") (class "Default")
      (node (ref "U$1") (pin "D6") (pinfunction "D6#_D6") (pintype "bidirectional"))
      (node (ref "U$2") (pin "PWMB") (pinfunction "PWMB_PWMB") (pintype "bidirectional"))
    )
    (net (code "61") (name "SCL") (class "Default")
      (node (ref "AUX2") (pin "3") (pinfunction "3_3") (pintype "passive"))
      (node (ref "AUX6") (pin "3") (pinfunction "3_3") (pintype "passive"))
      (node (ref "DISPLAY") (pin "2") (pinfunction "2_2") (pintype "passive"))
      (node (ref "MCP23017_INPUTS") (pin "8") (pinfunction "8_8") (pintype "passive"))
      (node (ref "R31") (pin "1") (pinfunction "1_1") (pintype "passive"))
      (node (ref "U$1") (pin "A5") (pinfunction "A5_A5") (pintype "bidirectional"))
    )
    (net (code "62") (name "SD1") (class "Default")
      (node (ref "SD1") (pin "3") (pinfunction "3_3") (pintype "passive"))
      (node (ref "U$1") (pin "D2") (pinfunction "D2_D2") (pintype "bidirectional"))
    )
    (net (code "63") (name "SD2") (class "Default")
      (node (ref "SD2") (pin "3") (pinfunction "3_3") (pintype "passive"))
      (node (ref "U$1") (pin "A1") (pinfunction "A1_A1") (pintype "bidirectional"))
    )
    (net (code "64") (name "SD3") (class "Default")
      (node (ref "SD3") (pin "3") (pinfunction "3_3") (pintype "passive"))
      (node (ref "U$1") (pin "A0") (pinfunction "A0_A0") (pintype "bidirectional"))
    )
    (net (code "65") (name "SD4") (class "Default")
      (node (ref "SD4") (pin "3") (pinfunction "3_3") (pintype "passive"))
      (node (ref "U$1") (pin "D7") (pinfunction "D7_D7") (pintype "bidirectional"))
    )
    (net (code "66") (name "SD5") (class "Default")
      (node (ref "SD5") (pin "3") (pinfunction "3_3") (pintype "passive"))
      (node (ref "U$1") (pin "D8") (pinfunction "D8_D8") (pintype "bidirectional"))
    )
    (net (code "67") (name "SD6") (class "Default")
      (node (ref "SD6") (pin "3") (pinfunction "3_3") (pintype "passive"))
      (node (ref "U$1") (pin "D9") (pinfunction "D9#_D9") (pintype "bidirectional"))
    )
    (net (code "68") (name "SDA") (class "Default")
      (node (ref "AUX2") (pin "2") (pinfunction "2_2") (pintype "passive"))
      (node (ref "AUX6") (pin "2") (pinfunction "2_2") (pintype "passive"))
      (node (ref "DISPLAY") (pin "1") (pinfunction "1_1") (pintype "passive"))
      (node (ref "MCP23017_INPUTS") (pin "7") (pinfunction "7_7") (pintype "passive"))
      (node (ref "R32") (pin "1") (pinfunction "1_1") (pintype "passive"))
      (node (ref "U$1") (pin "A4") (pinfunction "A4_A4") (pintype "bidirectional"))
    )
    (net (code "69") (name "SL1") (class "Default")
      (node (ref "SL1") (pin "3") (pinfunction "3_3") (pintype "passive"))
      (node (ref "U$1") (pin "A6") (pinfunction "A6_A6") (pintype "bidirectional"))
    )
    (net (code "70") (name "SL2") (class "Default")
      (node (ref "SL2") (pin "3") (pinfunction "3_3") (pintype "passive"))
      (node (ref "U$1") (pin "A3") (pinfunction "A3_A3") (pintype "bidirectional"))
    )
    (net (code "71") (name "SL3") (class "Default")
      (node (ref "SL3") (pin "3") (pinfunction "3_3") (pintype "passive"))
      (node (ref "U$1") (pin "A2") (pinfunction "A2_A2") (pintype "bidirectional"))
    )
    (net (code "72") (name "SS") (class "Default")
      (node (ref "AUX1") (pin "3") (pinfunction "3_3") (pintype "passive"))
      (node (ref "AUX5") (pin "3") (pinfunction "3_3") (pintype "passive"))
      (node (ref "SERVO2") (pin "1") (pinfunction "1_1") (pintype "passive"))
      (node (ref "U$1") (pin "D10") (pinfunction "D10#_D10") (pintype "bidirectional"))
    )
    (net (code "73") (name "VCCARD") (class "Default")
      (node (ref "AUX3") (pin "3") (pinfunction "3_3") (pintype "passive"))
      (node (ref "AUX7") (pin "3") (pinfunction "3_3") (pintype "passive"))
      (node (ref "B1") (pin "2") (pinfunction "2_2") (pintype "passive"))
      (node (ref "B1B") (pin "2") (pinfunction "2_2") (pintype "passive"))
      (node (ref "BLUETOOTH1") (pin "4") (pinfunction "4_4") (pintype "passive"))
      (node (ref "DISPLAY") (pin "3") (pinfunction "3_3") (pintype "passive"))
      (node (ref "MCP23017_INPUTS") (pin "10") (pinfunction "10_10") (pintype "passive"))
      (node (ref "MCP23017_OUTPUTS") (pin "20") (pinfunction "20_20") (pintype "passive"))
      (node (ref "R2") (pin "2") (pinfunction "2_2") (pintype "passive"))
      (node (ref "R31") (pin "2") (pinfunction "2_2") (pintype "passive"))
      (node (ref "R32") (pin "2") (pinfunction "2_2") (pintype "passive"))
      (node (ref "S1") (pin "1") (pinfunction "1_1") (pintype "passive"))
      (node (ref "S2") (pin "1") (pinfunction "1_1") (pintype "passive"))
      (node (ref "S3") (pin "1") (pinfunction "1_1") (pintype "passive"))
      (node (ref "S4") (pin "1") (pinfunction "1_1") (pintype "passive"))
      (node (ref "SERIAL/IR") (pin "4") (pinfunction "4_4") (pintype "passive"))
      (node (ref "U$1") (pin "+5V") (pinfunction "+5V_+5V") (pintype "bidirectional"))
    )
    (net (code "74") (name "VCCSENS") (class "Default")
      (node (ref "7805") (pin "OUT") (pinfunction "OUT_OUT") (pintype "output"))
      (node (ref "AUX3") (pin "2") (pinfunction "2_2") (pintype "passive"))
      (node (ref "AUX7") (pin "2") (pinfunction "2_2") (pintype "passive"))
      (node (ref "C2") (pin "1") (pinfunction "1_1") (pintype "passive"))
      (node (ref "C3") (pin "+") (pinfunction "+_+") (pintype "passive"))
      (node (ref "R6") (pin "2") (pinfunction "2_2") (pintype "passive"))
      (node (ref "R7") (pin "2") (pinfunction "2_2") (pintype "passive"))
      (node (ref "SD1") (pin "1") (pinfunction "1_1") (pintype "passive"))
      (node (ref "SD2") (pin "1") (pinfunction "1_1") (pintype "passive"))
      (node (ref "SD3") (pin "1") (pinfunction "1_1") (pintype "passive"))
      (node (ref "SD4") (pin "1") (pinfunction "1_1") (pintype "passive"))
      (node (ref "SD5") (pin "1") (pinfunction "1_1") (pintype "passive"))
      (node (ref "SD6") (pin "1") (pinfunction "1_1") (pintype "passive"))
      (node (ref "SERVO1") (pin "2") (pinfunction "2_2") (pintype "passive"))
      (node (ref "SERVO2") (pin "2") (pinfunction "2_2") (pintype "passive"))
      (node (ref "SL1") (pin "2") (pinfunction "2_2") (pintype "passive"))
      (node (ref "SL2") (pin "2") (pinfunction "2_2") (pintype "passive"))
      (node (ref "SL3") (pin "2") (pinfunction "2_2") (pintype "passive"))
      (node (ref "U$2") (pin "STBY") (pinfunction "STBY_STBY") (pintype "bidirectional"))
      (node (ref "U$2") (pin "VCC") (pinfunction "VCC_VCC") (pintype "bidirectional"))
    )
    (net (code "75") (name "VINMOT") (class "Default")
      (node (ref "C4") (pin "+") (pinfunction "+_+") (pintype "passive"))
      (node (ref "GENERAL_SWITCH") (pin "B1") (pinfunction "B1_B1") (pintype "bidirectional"))
      (node (ref "U$2") (pin "VM") (pinfunction "VM_VM") (pintype "bidirectional"))
    )
    (net (code "76") (name "VINVREG") (class "Default")
      (node (ref "+BAT2") (pin "2") (pinfunction "2_2") (pintype "passive"))
      (node (ref "7805") (pin "IN") (pinfunction "IN_IN") (pintype "input"))
      (node (ref "C1") (pin "1") (pinfunction "1_1") (pintype "passive"))
      (node (ref "GENERAL_SWITCH") (pin "B2") (pinfunction "B2_B2") (pintype "bidirectional"))
      (node (ref "GENERAL_SWITCH1") (pin "B1") (pinfunction "B1_B1") (pintype "bidirectional"))
      (node (ref "GENERAL_SWITCH1") (pin "B2") (pinfunction "B2_B2") (pintype "bidirectional"))
      (node (ref "R4") (pin "1") (pinfunction "1_1") (pintype "passive"))
      (node (ref "U$1") (pin "VIN") (pinfunction "VIN_VIN") (pintype "bidirectional"))
    )
    (net (code "77") (name "VREFBAT") (class "Default")
      (node (ref "R4") (pin "2") (pinfunction "2_2") (pintype "passive"))
      (node (ref "R5") (pin "1") (pinfunction "1_1") (pintype "passive"))
      (node (ref "U$1") (pin "A7") (pinfunction "A7_A7") (pintype "bidirectional"))
    )
    (net (code "78") (name "unconnected-(U$1-Pad3V3)") (class "Default")
      (node (ref "U$1") (pin "3V3") (pinfunction "3V3_3V3") (pintype "bidirectional"))
    )
    (net (code "79") (name "unconnected-(U$1-PadAREF)") (class "Default")
      (node (ref "U$1") (pin "AREF") (pinfunction "AREF_AREF") (pintype "bidirectional"))
    )
    (net (code "80") (name "unconnected-(U$1-PadRESET)") (class "Default")
      (node (ref "U$1") (pin "RESET") (pinfunction "RESET_RESET") (pintype "bidirectional"))
    )
    (net (code "81") (name "unconnected-(U$1-PadRESET1)") (class "Default")
      (node (ref "U$1") (pin "RESET1") (pinfunction "RESET1_RESET1") (pintype "bidirectional"))
    )
  )
)
